# I2C_Expanders.net
KiCad netlist of a schematic drawn in Altium Designer
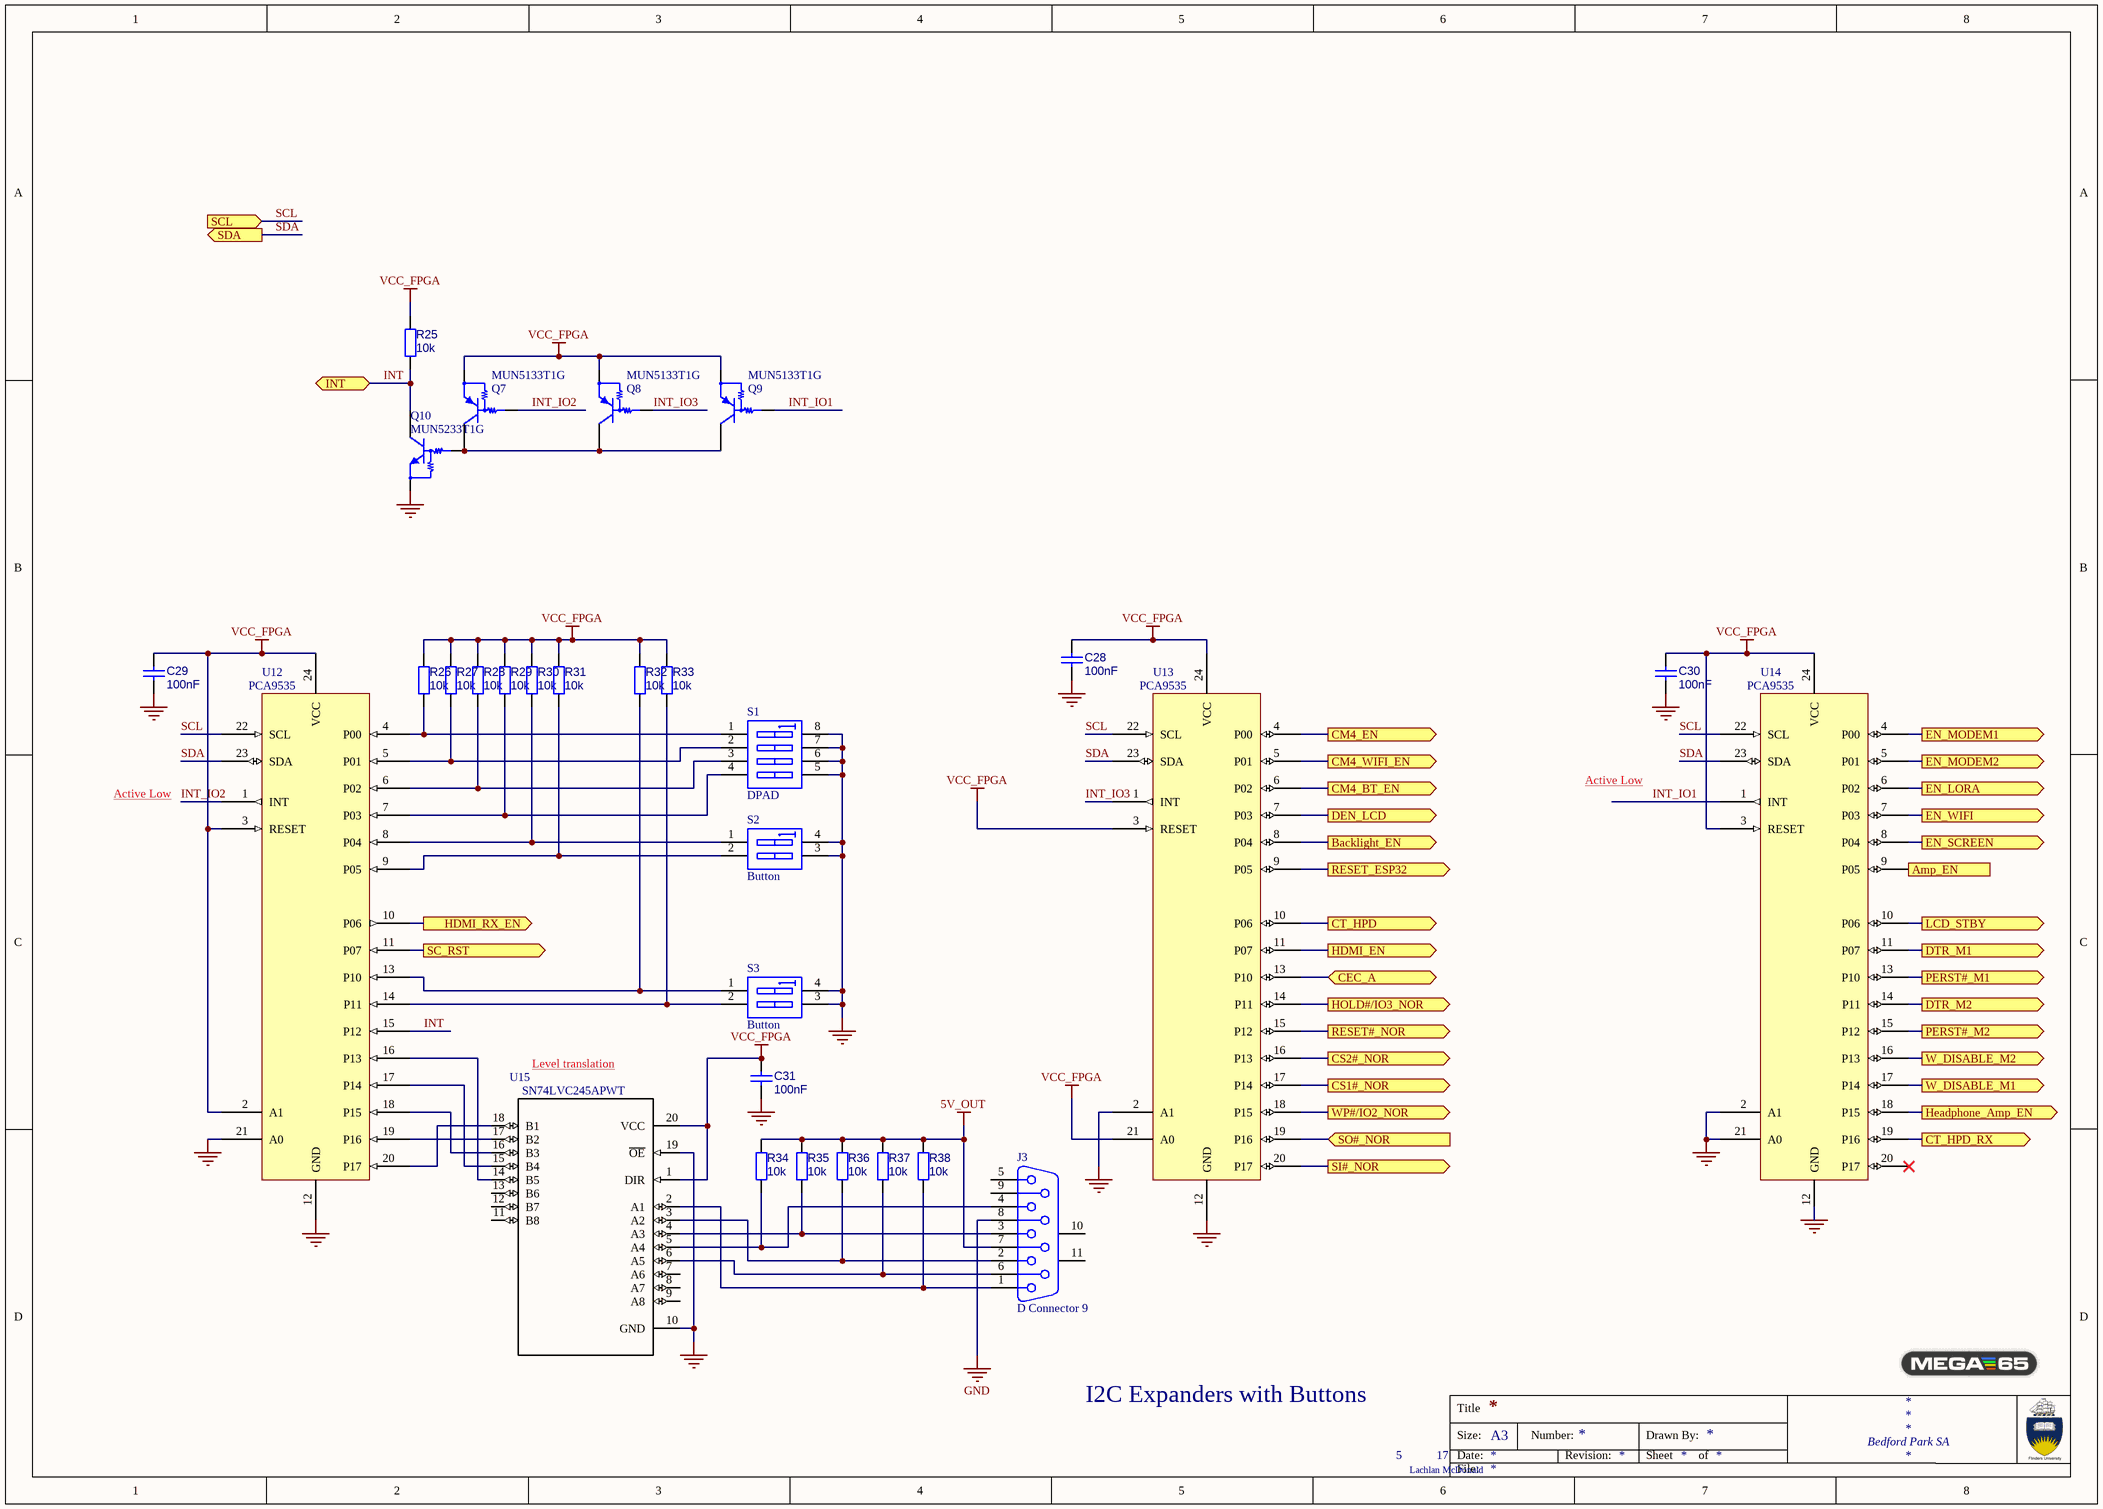
[diagram p0: I2C Expanders.SchDoc]

(export (version "E")
  (design (tool "Eeschema 10.0.6"))
  (components
    (comp (ref "C28")
      (value "100nF")
      (footprint "0603_CAP UF HD")
      (description "Capacitor")
      (libsource (lib "Workshop Library 2010_06_24") (part "Cap"))
    )
    (comp (ref "C29")
      (value "100nF")
      (footprint "0603_CAP UF HD")
      (description "Capacitor")
      (libsource (lib "Workshop Library 2010_06_24") (part "Cap"))
    )
    (comp (ref "C30")
      (value "100nF")
      (footprint "0603_CAP UF HD")
      (description "Capacitor")
      (libsource (lib "Workshop Library 2010_06_24") (part "Cap"))
    )
    (comp (ref "C31")
      (value "100nF")
      (footprint "0603_CAP UF HD")
      (description "Capacitor")
      (libsource (lib "Workshop Library 2010_06_24") (part "Cap"))
    )
    (comp (ref "J3")
      (value "D Connector 9")
      (footprint "DB9 Right Angle Through-Hole Male")
      (description "Receptacle Assembly, 9 Position, Right Angle")
      (fields (field (name "MANUFACTURER") "Assman WSW"))
      (libsource (lib "Miscellaneous Connectors") (part "D Connector 9"))
    )
    (comp (ref "Q7")
      (value "MUN5133T1G")
      (footprint "SC70-3 (SOT-323)")
      (description "PNP Bipolar Transistor, Prebiased")
      (fields (field (name "MANUFACTURER") "ON Semiconductor"))
      (libsource (lib "Workshop Library 2010_06_24") (part "Transistor PNP Prebiased"))
    )
    (comp (ref "Q8")
      (value "MUN5133T1G")
      (footprint "SC70-3 (SOT-323)")
      (description "PNP Bipolar Transistor, Prebiased")
      (fields (field (name "MANUFACTURER") "ON Semiconductor"))
      (libsource (lib "Workshop Library 2010_06_24") (part "Transistor PNP Prebiased"))
    )
    (comp (ref "Q9")
      (value "MUN5133T1G")
      (footprint "SC70-3 (SOT-323)")
      (description "PNP Bipolar Transistor, Prebiased")
      (fields (field (name "MANUFACTURER") "ON Semiconductor"))
      (libsource (lib "Workshop Library 2010_06_24") (part "Transistor PNP Prebiased"))
    )
    (comp (ref "Q10")
      (value "MUN5233T1G")
      (footprint "SC70-3 (SOT-323)")
      (description "NPN Bipolar Transistor, Prebiased")
      (fields (field (name "MANUFACTURER") "ON Semiconductor"))
      (libsource (lib "Workshop Library 2010_06_24") (part "Transistor NPN Prebiased"))
    )
    (comp (ref "R25")
      (value "10k")
      (footprint "0603-RESISTOR HD")
      (description "Resistor")
      (libsource (lib "") (part "Resistor_1"))
    )
    (comp (ref "R26")
      (value "10k")
      (footprint "0603-RESISTOR HD")
      (description "Resistor")
      (libsource (lib "Workshop Library 2010_06_24") (part "Resistor"))
    )
    (comp (ref "R27")
      (value "10k")
      (footprint "0603-RESISTOR HD")
      (description "Resistor")
      (libsource (lib "Workshop Library 2010_06_24") (part "Resistor"))
    )
    (comp (ref "R28")
      (value "10k")
      (footprint "0603-RESISTOR HD")
      (description "Resistor")
      (libsource (lib "Workshop Library 2010_06_24") (part "Resistor"))
    )
    (comp (ref "R29")
      (value "10k")
      (footprint "0603-RESISTOR HD")
      (description "Resistor")
      (libsource (lib "Workshop Library 2010_06_24") (part "Resistor"))
    )
    (comp (ref "R30")
      (value "10k")
      (footprint "0603-RESISTOR HD")
      (description "Resistor")
      (libsource (lib "Workshop Library 2010_06_24") (part "Resistor"))
    )
    (comp (ref "R31")
      (value "10k")
      (footprint "0603-RESISTOR HD")
      (description "Resistor")
      (libsource (lib "Workshop Library 2010_06_24") (part "Resistor"))
    )
    (comp (ref "R32")
      (value "10k")
      (footprint "0603-RESISTOR HD")
      (description "Resistor")
      (libsource (lib "Workshop Library 2010_06_24") (part "Resistor"))
    )
    (comp (ref "R33")
      (value "10k")
      (footprint "0603-RESISTOR HD")
      (description "Resistor")
      (libsource (lib "Workshop Library 2010_06_24") (part "Resistor"))
    )
    (comp (ref "R34")
      (value "10k")
      (footprint "0603-RESISTOR HD")
      (description "Resistor")
      (libsource (lib "MEGAphone") (part "Resistor"))
    )
    (comp (ref "R35")
      (value "10k")
      (footprint "0603-RESISTOR HD")
      (description "Resistor")
      (libsource (lib "MEGAphone") (part "Resistor"))
    )
    (comp (ref "R36")
      (value "10k")
      (footprint "0603-RESISTOR HD")
      (description "Resistor")
      (libsource (lib "MEGAphone") (part "Resistor"))
    )
    (comp (ref "R37")
      (value "10k")
      (footprint "0603-RESISTOR HD")
      (description "Resistor")
      (libsource (lib "MEGAphone") (part "Resistor"))
    )
    (comp (ref "R38")
      (value "10k")
      (footprint "0603-RESISTOR HD")
      (description "Resistor")
      (libsource (lib "MEGAphone") (part "Resistor"))
    )
    (comp (ref "S1")
      (value "DPAD")
      (footprint "DPAD Gameboy V2")
      (description "DIP Switch, 4 Position, SPST")
      (libsource (lib "Miscellaneous Devices") (part "SW DIP-4"))
    )
    (comp (ref "S2")
      (value "Button")
      (footprint "Buttons Gameboy v2")
      (description "DIP Switch, 2 Position, SPST")
      (libsource (lib "Miscellaneous Devices") (part "SW DIP-2"))
    )
    (comp (ref "S3")
      (value "Button")
      (footprint "Buttons Gameboy v2")
      (description "DIP Switch, 2 Position, SPST")
      (libsource (lib "Miscellaneous Devices") (part "SW DIP-2"))
    )
    (comp (ref "U12")
      (value "PCA9535")
      (footprint "PW0024A_M")
      (fields (field (name "MANUFACTURER") "NXP"))
      (libsource (lib "Schlib1") (part "TCA9539"))
    )
    (comp (ref "U13")
      (value "PCA9535")
      (footprint "PW0024A_M")
      (fields (field (name "MANUFACTURER") "NXP"))
      (libsource (lib "Schlib1") (part "TCA9539"))
    )
    (comp (ref "U14")
      (value "PCA9535")
      (footprint "PW0024A_M")
      (fields (field (name "MANUFACTURER") "NXP"))
      (libsource (lib "Schlib1") (part "TCA9539"))
    )
    (comp (ref "U15")
      (value "SN74LVC245APWT")
      (footprint "DGV20_M")
      (description "Octal Bus Transceiver With 3-State Outputs 20-TSSOP -40 to 125")
      (fields (field (name "MANUFACTURER") "Texas Instruments"))
      (libsource (lib "SN74LVC245APWT") (part "SN74LVC245APWT"))
    )
  )
  (nets
    (net (code "1") (name "/Amp_EN") (class "Default")
      (node (ref "U14") (pin "9") (pinfunction "P05_9") (pintype "bidirectional"))
    )
    (net (code "2") (name "/Backlight_EN") (class "Default")
      (node (ref "U13") (pin "8") (pinfunction "P04_8") (pintype "bidirectional"))
    )
    (net (code "3") (name "/CEC_A") (class "Default")
      (node (ref "U13") (pin "13") (pinfunction "P10_13") (pintype "bidirectional"))
    )
    (net (code "4") (name "/CM4_BT_EN") (class "Default")
      (node (ref "U13") (pin "6") (pinfunction "P02_6") (pintype "bidirectional"))
    )
    (net (code "5") (name "/CM4_EN") (class "Default")
      (node (ref "U13") (pin "4") (pinfunction "P00_4") (pintype "bidirectional"))
    )
    (net (code "6") (name "/CM4_WIFI_EN") (class "Default")
      (node (ref "U13") (pin "5") (pinfunction "P01_5") (pintype "bidirectional"))
    )
    (net (code "7") (name "/CS1#_NOR") (class "Default")
      (node (ref "U13") (pin "17") (pinfunction "P14_17") (pintype "bidirectional"))
    )
    (net (code "8") (name "/CS2#_NOR") (class "Default")
      (node (ref "U13") (pin "16") (pinfunction "P13_16") (pintype "bidirectional"))
    )
    (net (code "9") (name "/CT_HPD") (class "Default")
      (node (ref "U13") (pin "10") (pinfunction "P06_10") (pintype "bidirectional"))
    )
    (net (code "10") (name "/CT_HPD_RX") (class "Default")
      (node (ref "U14") (pin "19") (pinfunction "P16_19") (pintype "bidirectional"))
    )
    (net (code "11") (name "/DEN_LCD") (class "Default")
      (node (ref "U13") (pin "7") (pinfunction "P03_7") (pintype "bidirectional"))
    )
    (net (code "12") (name "/DTR_M1") (class "Default")
      (node (ref "U14") (pin "11") (pinfunction "P07_11") (pintype "bidirectional"))
    )
    (net (code "13") (name "/DTR_M2") (class "Default")
      (node (ref "U14") (pin "14") (pinfunction "P11_14") (pintype "bidirectional"))
    )
    (net (code "14") (name "/EN_LORA") (class "Default")
      (node (ref "U14") (pin "6") (pinfunction "P02_6") (pintype "bidirectional"))
    )
    (net (code "15") (name "/EN_MODEM1") (class "Default")
      (node (ref "U14") (pin "4") (pinfunction "P00_4") (pintype "bidirectional"))
    )
    (net (code "16") (name "/EN_MODEM2") (class "Default")
      (node (ref "U14") (pin "5") (pinfunction "P01_5") (pintype "bidirectional"))
    )
    (net (code "17") (name "/EN_SCREEN") (class "Default")
      (node (ref "U14") (pin "8") (pinfunction "P04_8") (pintype "bidirectional"))
    )
    (net (code "18") (name "/EN_WIFI") (class "Default")
      (node (ref "U14") (pin "7") (pinfunction "P03_7") (pintype "bidirectional"))
    )
    (net (code "19") (name "/HDMI_EN") (class "Default")
      (node (ref "U13") (pin "11") (pinfunction "P07_11") (pintype "bidirectional"))
    )
    (net (code "20") (name "/HDMI_RX_EN") (class "Default")
      (node (ref "U12") (pin "10") (pinfunction "P06_10") (pintype "bidirectional"))
    )
    (net (code "21") (name "/HOLD#{slash}IO3_NOR") (class "Default")
      (node (ref "U13") (pin "14") (pinfunction "P11_14") (pintype "bidirectional"))
    )
    (net (code "22") (name "/Headphone_Amp_EN") (class "Default")
      (node (ref "U14") (pin "18") (pinfunction "P15_18") (pintype "bidirectional"))
    )
    (net (code "23") (name "/INT") (class "Default")
      (node (ref "Q10") (pin "3") (pinfunction "C_3") (pintype "passive"))
      (node (ref "R25") (pin "1") (pinfunction "1_1") (pintype "passive"))
      (node (ref "U12") (pin "15") (pinfunction "P12_15") (pintype "bidirectional"))
    )
    (net (code "24") (name "/INT_IO1") (class "Default")
      (node (ref "Q9") (pin "1") (pinfunction "B_1") (pintype "passive"))
      (node (ref "U14") (pin "1") (pinfunction "INT_1") (pintype "output"))
    )
    (net (code "25") (name "/INT_IO2") (class "Default")
      (node (ref "Q7") (pin "1") (pinfunction "B_1") (pintype "passive"))
      (node (ref "U12") (pin "1") (pinfunction "INT_1") (pintype "output"))
    )
    (net (code "26") (name "/INT_IO3") (class "Default")
      (node (ref "Q8") (pin "1") (pinfunction "B_1") (pintype "passive"))
      (node (ref "U13") (pin "1") (pinfunction "INT_1") (pintype "output"))
    )
    (net (code "27") (name "/LCD_STBY") (class "Default")
      (node (ref "U14") (pin "10") (pinfunction "P06_10") (pintype "bidirectional"))
    )
    (net (code "28") (name "/PERST#_M1") (class "Default")
      (node (ref "U14") (pin "13") (pinfunction "P10_13") (pintype "bidirectional"))
    )
    (net (code "29") (name "/PERST#_M2") (class "Default")
      (node (ref "U14") (pin "15") (pinfunction "P12_15") (pintype "bidirectional"))
    )
    (net (code "30") (name "/RESET#_NOR") (class "Default")
      (node (ref "U13") (pin "15") (pinfunction "P12_15") (pintype "bidirectional"))
    )
    (net (code "31") (name "/RESET_ESP32") (class "Default")
      (node (ref "U13") (pin "9") (pinfunction "P05_9") (pintype "bidirectional"))
    )
    (net (code "32") (name "/SCL") (class "Default")
      (node (ref "U12") (pin "22") (pinfunction "SCL_22") (pintype "input"))
      (node (ref "U13") (pin "22") (pinfunction "SCL_22") (pintype "input"))
      (node (ref "U14") (pin "22") (pinfunction "SCL_22") (pintype "input"))
    )
    (net (code "33") (name "/SC_RST") (class "Default")
      (node (ref "U12") (pin "11") (pinfunction "P07_11") (pintype "bidirectional"))
    )
    (net (code "34") (name "/SDA") (class "Default")
      (node (ref "U12") (pin "23") (pinfunction "SDA_23") (pintype "bidirectional"))
      (node (ref "U13") (pin "23") (pinfunction "SDA_23") (pintype "bidirectional"))
      (node (ref "U14") (pin "23") (pinfunction "SDA_23") (pintype "bidirectional"))
    )
    (net (code "35") (name "/SI#_NOR") (class "Default")
      (node (ref "U13") (pin "20") (pinfunction "P17_20") (pintype "bidirectional"))
    )
    (net (code "36") (name "/SO#_NOR") (class "Default")
      (node (ref "U13") (pin "19") (pinfunction "P16_19") (pintype "bidirectional"))
    )
    (net (code "37") (name "/WP#{slash}IO2_NOR") (class "Default")
      (node (ref "U13") (pin "18") (pinfunction "P15_18") (pintype "bidirectional"))
    )
    (net (code "38") (name "/W_DISABLE_M1") (class "Default")
      (node (ref "U14") (pin "17") (pinfunction "P14_17") (pintype "bidirectional"))
    )
    (net (code "39") (name "/W_DISABLE_M2") (class "Default")
      (node (ref "U14") (pin "16") (pinfunction "P13_16") (pintype "bidirectional"))
    )
    (net (code "40") (name "5V_OUT") (class "Default")
      (node (ref "J3") (pin "7") (pinfunction "7_7") (pintype "passive"))
      (node (ref "R34") (pin "1") (pinfunction "1_1") (pintype "passive"))
      (node (ref "R35") (pin "1") (pinfunction "1_1") (pintype "passive"))
      (node (ref "R36") (pin "1") (pinfunction "1_1") (pintype "passive"))
      (node (ref "R37") (pin "1") (pinfunction "1_1") (pintype "passive"))
      (node (ref "R38") (pin "1") (pinfunction "1_1") (pintype "passive"))
    )
    (net (code "41") (name "GND") (class "Default")
      (node (ref "C28") (pin "2") (pinfunction "2_2") (pintype "passive"))
      (node (ref "C29") (pin "2") (pinfunction "2_2") (pintype "passive"))
      (node (ref "C30") (pin "2") (pinfunction "2_2") (pintype "passive"))
      (node (ref "C31") (pin "2") (pinfunction "2_2") (pintype "passive"))
      (node (ref "J3") (pin "8") (pinfunction "8_8") (pintype "passive"))
      (node (ref "Q10") (pin "1") (pinfunction "E_1") (pintype "passive"))
      (node (ref "S1") (pin "5") (pinfunction "B4_5") (pintype "passive"))
      (node (ref "S1") (pin "6") (pinfunction "B3_6") (pintype "passive"))
      (node (ref "S1") (pin "7") (pinfunction "B2_7") (pintype "passive"))
      (node (ref "S1") (pin "8") (pinfunction "B1_8") (pintype "passive"))
      (node (ref "S2") (pin "3") (pinfunction "B2_3") (pintype "passive"))
      (node (ref "S2") (pin "4") (pinfunction "B1_4") (pintype "passive"))
      (node (ref "S3") (pin "3") (pinfunction "B2_3") (pintype "passive"))
      (node (ref "S3") (pin "4") (pinfunction "B1_4") (pintype "passive"))
      (node (ref "U12") (pin "12") (pinfunction "GND_12") (pintype "passive"))
      (node (ref "U12") (pin "21") (pinfunction "A0_21") (pintype "passive"))
      (node (ref "U13") (pin "12") (pinfunction "GND_12") (pintype "passive"))
      (node (ref "U13") (pin "2") (pinfunction "A1_2") (pintype "passive"))
      (node (ref "U14") (pin "12") (pinfunction "GND_12") (pintype "passive"))
      (node (ref "U14") (pin "2") (pinfunction "A1_2") (pintype "passive"))
      (node (ref "U14") (pin "21") (pinfunction "A0_21") (pintype "passive"))
      (node (ref "U15") (pin "10") (pinfunction "GND_10") (pintype "passive"))
      (node (ref "U15") (pin "19") (pinfunction "~{OE}_19") (pintype "input"))
    )
    (net (code "42") (name "Net-(Q10-B)") (class "Default")
      (node (ref "Q10") (pin "2") (pinfunction "B_2") (pintype "passive"))
      (node (ref "Q7") (pin "3") (pinfunction "C_3") (pintype "passive"))
      (node (ref "Q8") (pin "3") (pinfunction "C_3") (pintype "passive"))
      (node (ref "Q9") (pin "3") (pinfunction "C_3") (pintype "passive"))
    )
    (net (code "43") (name "Net-(S1-A1)") (class "Default")
      (node (ref "R26") (pin "2") (pinfunction "2_2") (pintype "passive"))
      (node (ref "S1") (pin "1") (pinfunction "A1_1") (pintype "passive"))
      (node (ref "U12") (pin "4") (pinfunction "P00_4") (pintype "bidirectional"))
    )
    (net (code "44") (name "Net-(S1-A2)") (class "Default")
      (node (ref "R27") (pin "2") (pinfunction "2_2") (pintype "passive"))
      (node (ref "S1") (pin "2") (pinfunction "A2_2") (pintype "passive"))
      (node (ref "U12") (pin "5") (pinfunction "P01_5") (pintype "bidirectional"))
    )
    (net (code "45") (name "Net-(S1-A3)") (class "Default")
      (node (ref "R28") (pin "2") (pinfunction "2_2") (pintype "passive"))
      (node (ref "S1") (pin "3") (pinfunction "A3_3") (pintype "passive"))
      (node (ref "U12") (pin "6") (pinfunction "P02_6") (pintype "bidirectional"))
    )
    (net (code "46") (name "Net-(S1-A4)") (class "Default")
      (node (ref "R29") (pin "2") (pinfunction "2_2") (pintype "passive"))
      (node (ref "S1") (pin "4") (pinfunction "A4_4") (pintype "passive"))
      (node (ref "U12") (pin "7") (pinfunction "P03_7") (pintype "bidirectional"))
    )
    (net (code "47") (name "Net-(S2-A1)") (class "Default")
      (node (ref "R30") (pin "2") (pinfunction "2_2") (pintype "passive"))
      (node (ref "S2") (pin "1") (pinfunction "A1_1") (pintype "passive"))
      (node (ref "U12") (pin "8") (pinfunction "P04_8") (pintype "bidirectional"))
    )
    (net (code "48") (name "Net-(S2-A2)") (class "Default")
      (node (ref "R31") (pin "2") (pinfunction "2_2") (pintype "passive"))
      (node (ref "S2") (pin "2") (pinfunction "A2_2") (pintype "passive"))
      (node (ref "U12") (pin "9") (pinfunction "P05_9") (pintype "bidirectional"))
    )
    (net (code "49") (name "Net-(S3-A1)") (class "Default")
      (node (ref "R32") (pin "2") (pinfunction "2_2") (pintype "passive"))
      (node (ref "S3") (pin "1") (pinfunction "A1_1") (pintype "passive"))
      (node (ref "U12") (pin "13") (pinfunction "P10_13") (pintype "bidirectional"))
    )
    (net (code "50") (name "Net-(S3-A2)") (class "Default")
      (node (ref "R33") (pin "2") (pinfunction "2_2") (pintype "passive"))
      (node (ref "S3") (pin "2") (pinfunction "A2_2") (pintype "passive"))
      (node (ref "U12") (pin "14") (pinfunction "P11_14") (pintype "bidirectional"))
    )
    (net (code "51") (name "Net-(U12-P13)") (class "Default")
      (node (ref "U12") (pin "16") (pinfunction "P13_16") (pintype "bidirectional"))
      (node (ref "U15") (pin "14") (pinfunction "B5_14") (pintype "bidirectional"))
    )
    (net (code "52") (name "Net-(U12-P14)") (class "Default")
      (node (ref "U12") (pin "17") (pinfunction "P14_17") (pintype "bidirectional"))
      (node (ref "U15") (pin "15") (pinfunction "B4_15") (pintype "bidirectional"))
    )
    (net (code "53") (name "Net-(U12-P15)") (class "Default")
      (node (ref "U12") (pin "18") (pinfunction "P15_18") (pintype "bidirectional"))
      (node (ref "U15") (pin "16") (pinfunction "B3_16") (pintype "bidirectional"))
    )
    (net (code "54") (name "Net-(U12-P16)") (class "Default")
      (node (ref "U12") (pin "19") (pinfunction "P16_19") (pintype "bidirectional"))
      (node (ref "U15") (pin "17") (pinfunction "B2_17") (pintype "bidirectional"))
    )
    (net (code "55") (name "Net-(U12-P17)") (class "Default")
      (node (ref "U12") (pin "20") (pinfunction "P17_20") (pintype "bidirectional"))
      (node (ref "U15") (pin "18") (pinfunction "B1_18") (pintype "bidirectional"))
    )
    (net (code "56") (name "Net-(U15-A1)") (class "Default")
      (node (ref "J3") (pin "1") (pinfunction "1_1") (pintype "passive"))
      (node (ref "R38") (pin "2") (pinfunction "2_2") (pintype "passive"))
      (node (ref "U15") (pin "2") (pinfunction "A1_2") (pintype "bidirectional"))
    )
    (net (code "57") (name "Net-(U15-A2)") (class "Default")
      (node (ref "J3") (pin "2") (pinfunction "2_2") (pintype "passive"))
      (node (ref "R36") (pin "2") (pinfunction "2_2") (pintype "passive"))
      (node (ref "U15") (pin "3") (pinfunction "A2_3") (pintype "bidirectional"))
    )
    (net (code "58") (name "Net-(U15-A3)") (class "Default")
      (node (ref "J3") (pin "3") (pinfunction "3_3") (pintype "passive"))
      (node (ref "R35") (pin "2") (pinfunction "2_2") (pintype "passive"))
      (node (ref "U15") (pin "4") (pinfunction "A3_4") (pintype "bidirectional"))
    )
    (net (code "59") (name "Net-(U15-A4)") (class "Default")
      (node (ref "J3") (pin "4") (pinfunction "4_4") (pintype "passive"))
      (node (ref "R34") (pin "2") (pinfunction "2_2") (pintype "passive"))
      (node (ref "U15") (pin "5") (pinfunction "A4_5") (pintype "bidirectional"))
    )
    (net (code "60") (name "Net-(U15-A5)") (class "Default")
      (node (ref "J3") (pin "6") (pinfunction "6_6") (pintype "passive"))
      (node (ref "R37") (pin "2") (pinfunction "2_2") (pintype "passive"))
      (node (ref "U15") (pin "6") (pinfunction "A5_6") (pintype "bidirectional"))
    )
    (net (code "61") (name "VCC_FPGA") (class "Default")
      (node (ref "C28") (pin "1") (pinfunction "1_1") (pintype "passive"))
      (node (ref "C29") (pin "1") (pinfunction "1_1") (pintype "passive"))
      (node (ref "C30") (pin "1") (pinfunction "1_1") (pintype "passive"))
      (node (ref "C31") (pin "1") (pinfunction "1_1") (pintype "passive"))
      (node (ref "Q7") (pin "2") (pinfunction "E_2") (pintype "passive"))
      (node (ref "Q8") (pin "2") (pinfunction "E_2") (pintype "passive"))
      (node (ref "Q9") (pin "2") (pinfunction "E_2") (pintype "passive"))
      (node (ref "R25") (pin "2") (pinfunction "2_2") (pintype "passive"))
      (node (ref "R26") (pin "1") (pinfunction "1_1") (pintype "passive"))
      (node (ref "R27") (pin "1") (pinfunction "1_1") (pintype "passive"))
      (node (ref "R28") (pin "1") (pinfunction "1_1") (pintype "passive"))
      (node (ref "R29") (pin "1") (pinfunction "1_1") (pintype "passive"))
      (node (ref "R30") (pin "1") (pinfunction "1_1") (pintype "passive"))
      (node (ref "R31") (pin "1") (pinfunction "1_1") (pintype "passive"))
      (node (ref "R32") (pin "1") (pinfunction "1_1") (pintype "passive"))
      (node (ref "R33") (pin "1") (pinfunction "1_1") (pintype "passive"))
      (node (ref "U12") (pin "2") (pinfunction "A1_2") (pintype "passive"))
      (node (ref "U12") (pin "24") (pinfunction "VCC_24") (pintype "passive"))
      (node (ref "U12") (pin "3") (pinfunction "RESET_3") (pintype "input"))
      (node (ref "U13") (pin "21") (pinfunction "A0_21") (pintype "passive"))
      (node (ref "U13") (pin "24") (pinfunction "VCC_24") (pintype "passive"))
      (node (ref "U13") (pin "3") (pinfunction "RESET_3") (pintype "input"))
      (node (ref "U14") (pin "24") (pinfunction "VCC_24") (pintype "passive"))
      (node (ref "U14") (pin "3") (pinfunction "RESET_3") (pintype "input"))
      (node (ref "U15") (pin "1") (pinfunction "DIR_1") (pintype "input"))
      (node (ref "U15") (pin "20") (pinfunction "VCC_20") (pintype "power_in"))
    )
    (net (code "62") (name "unconnected-(J3-MH1-Pad10)") (class "Default")
      (node (ref "J3") (pin "10") (pinfunction "MH1_10") (pintype "passive"))
    )
    (net (code "63") (name "unconnected-(J3-MH2-Pad11)") (class "Default")
      (node (ref "J3") (pin "11") (pinfunction "MH2_11") (pintype "passive"))
    )
    (net (code "64") (name "unconnected-(J3-Pad5)") (class "Default")
      (node (ref "J3") (pin "5") (pinfunction "5_5") (pintype "passive"))
    )
    (net (code "65") (name "unconnected-(J3-Pad9)") (class "Default")
      (node (ref "J3") (pin "9") (pinfunction "9_9") (pintype "passive"))
    )
    (net (code "66") (name "unconnected-(U14-P17-Pad20)") (class "Default")
      (node (ref "U14") (pin "20") (pinfunction "P17_20") (pintype "bidirectional+no_connect"))
    )
    (net (code "67") (name "unconnected-(U15-A6-Pad7)") (class "Default")
      (node (ref "U15") (pin "7") (pinfunction "A6_7") (pintype "bidirectional"))
    )
    (net (code "68") (name "unconnected-(U15-A7-Pad8)") (class "Default")
      (node (ref "U15") (pin "8") (pinfunction "A7_8") (pintype "bidirectional"))
    )
    (net (code "69") (name "unconnected-(U15-A8-Pad9)") (class "Default")
      (node (ref "U15") (pin "9") (pinfunction "A8_9") (pintype "bidirectional"))
    )
    (net (code "70") (name "unconnected-(U15-B6-Pad13)") (class "Default")
      (node (ref "U15") (pin "13") (pinfunction "B6_13") (pintype "bidirectional"))
    )
    (net (code "71") (name "unconnected-(U15-B7-Pad12)") (class "Default")
      (node (ref "U15") (pin "12") (pinfunction "B7_12") (pintype "bidirectional"))
    )
    (net (code "72") (name "unconnected-(U15-B8-Pad11)") (class "Default")
      (node (ref "U15") (pin "11") (pinfunction "B8_11") (pintype "bidirectional"))
    )
  )
)
